# lvc_v2.net
KiCad netlist of a schematic drawn in EAGLE
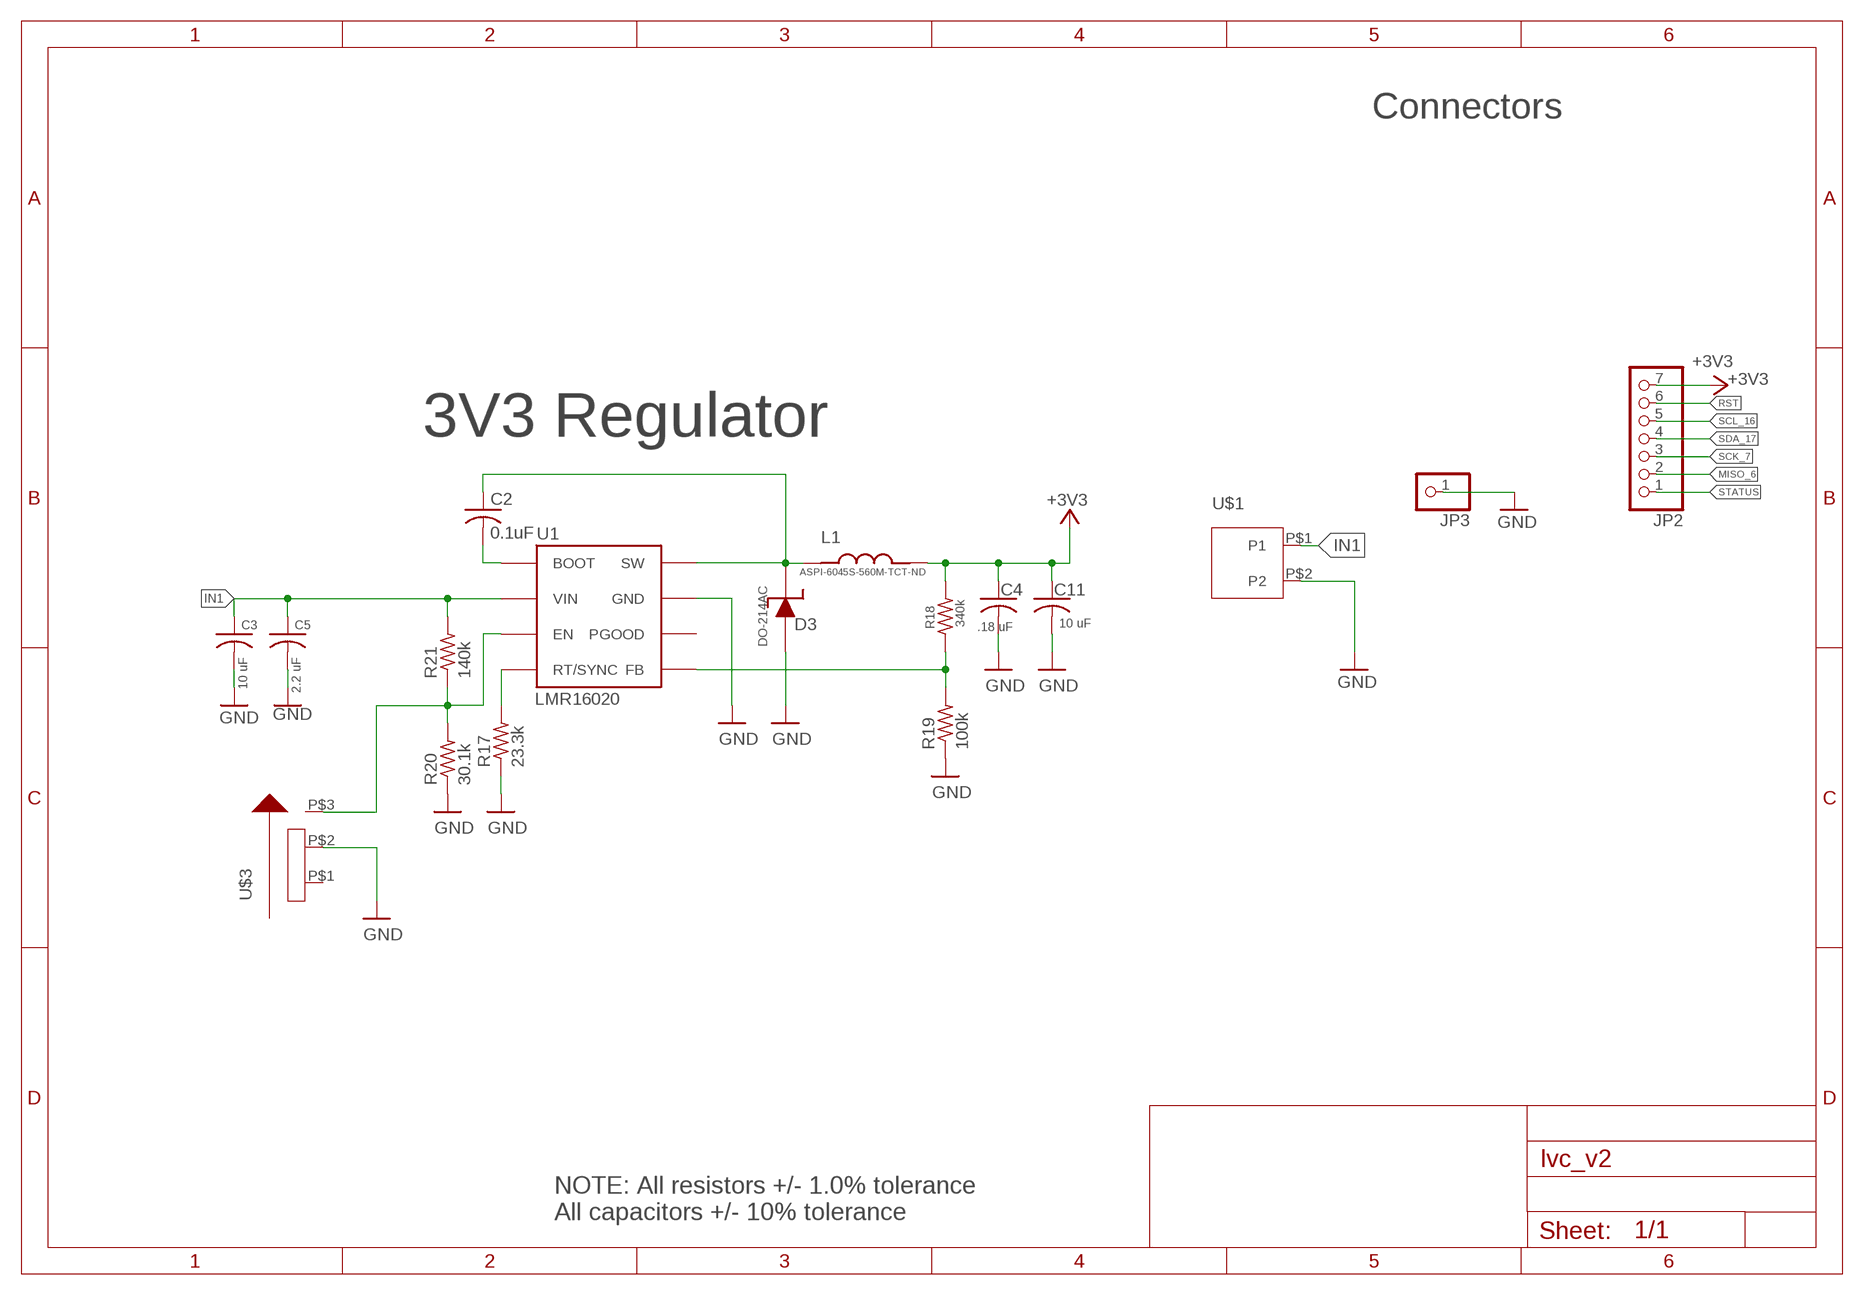
[diagram p0: schematic, sheet 1]

(export (version "E")
  (design (tool "Eeschema 10.0.6"))
  (components
    (comp (ref "C2")
      (value "0.1uF")
      (footprint "eagle-import:C0603")
      (libsource (lib "eagle-import") (part "C-USC0603"))
    )
    (comp (ref "C3")
      (value "10 uF")
      (footprint "eagle-import:C1210")
      (libsource (lib "eagle-import") (part "C-USC1210"))
    )
    (comp (ref "C4")
      (value ".18 uF")
      (footprint "eagle-import:C0603")
      (libsource (lib "eagle-import") (part "C-USC0603"))
    )
    (comp (ref "C5")
      (value "2.2 uF")
      (footprint "eagle-import:C1210")
      (libsource (lib "eagle-import") (part "C-USC1210"))
    )
    (comp (ref "C11")
      (value "10 uF")
      (footprint "eagle-import:C0603")
      (libsource (lib "eagle-import") (part "C-USC0603"))
    )
    (comp (ref "D3")
      (value "DO-214AC")
      (footprint "eagle-import:DO-214AC")
      (libsource (lib "eagle-import") (part "DO-214AC"))
    )
    (comp (ref "JP2")
      (value "PINHD-1X7")
      (footprint "eagle-import:1X07")
      (libsource (lib "eagle-import") (part "PINHD-1X7"))
    )
    (comp (ref "JP3")
      (value "PINHD-1X1")
      (footprint "eagle-import:1X01")
      (libsource (lib "eagle-import") (part "PINHD-1X1"))
    )
    (comp (ref "L1")
      (value "ASPI-6045S-560M-TCT-ND")
      (footprint "eagle-import:ABRACON")
      (libsource (lib "eagle-import") (part "ASPI-6045S-560M-TCT-ND"))
    )
    (comp (ref "R17")
      (value "23.3k")
      (footprint "eagle-import:R0603")
      (libsource (lib "eagle-import") (part "R-US_R0603"))
    )
    (comp (ref "R18")
      (value "340k")
      (footprint "eagle-import:R0603")
      (libsource (lib "eagle-import") (part "R-US_R0603"))
    )
    (comp (ref "R19")
      (value "100k")
      (footprint "eagle-import:R0603")
      (libsource (lib "eagle-import") (part "R-US_R0603"))
    )
    (comp (ref "R20")
      (value "30.1k")
      (footprint "eagle-import:R0603")
      (libsource (lib "eagle-import") (part "R-US_R0603"))
    )
    (comp (ref "R21")
      (value "140k")
      (footprint "eagle-import:R0603")
      (libsource (lib "eagle-import") (part "R-US_R0603"))
    )
    (comp (ref "U$1")
      (value "559350210")
      (footprint "eagle-import:559350210")
      (libsource (lib "eagle-import") (part "559350210"))
    )
    (comp (ref "U$3")
      (value "CL-SB-12B-01")
      (footprint "eagle-import:CL-SB-12B-01")
      (libsource (lib "eagle-import") (part "CL-SB-12B-01"))
    )
    (comp (ref "U1")
      (value "LMR16020")
      (footprint "eagle-import:SO8")
      (libsource (lib "eagle-import") (part "LMR16020"))
    )
  )
  (nets
    (net (code "1") (name "+3V3") (class "Default")
      (node (ref "C11") (pin "1") (pinfunction "1_1") (pintype "passive"))
      (node (ref "C4") (pin "1") (pinfunction "1_1") (pintype "passive"))
      (node (ref "JP2") (pin "7") (pinfunction "7_7") (pintype "passive"))
      (node (ref "L1") (pin "P$2") (pinfunction "P$2_P$2") (pintype "bidirectional"))
      (node (ref "R18") (pin "2") (pinfunction "2_2") (pintype "passive"))
    )
    (net (code "2") (name "GND") (class "Default")
      (node (ref "C11") (pin "2") (pinfunction "2_2") (pintype "passive"))
      (node (ref "C3") (pin "2") (pinfunction "2_2") (pintype "passive"))
      (node (ref "C4") (pin "2") (pinfunction "2_2") (pintype "passive"))
      (node (ref "C5") (pin "2") (pinfunction "2_2") (pintype "passive"))
      (node (ref "D3") (pin "P$1") (pinfunction "P$1_P$1") (pintype "bidirectional"))
      (node (ref "JP3") (pin "1") (pinfunction "1_1") (pintype "passive"))
      (node (ref "R17") (pin "1") (pinfunction "1_1") (pintype "passive"))
      (node (ref "R19") (pin "1") (pinfunction "1_1") (pintype "passive"))
      (node (ref "R20") (pin "1") (pinfunction "1_1") (pintype "passive"))
      (node (ref "U$1") (pin "P$2") (pinfunction "P2_P$2") (pintype "bidirectional"))
      (node (ref "U$3") (pin "P$2") (pinfunction "P2_P$2") (pintype "bidirectional"))
      (node (ref "U1") (pin "P$7") (pinfunction "GND_P$7") (pintype "bidirectional"))
      (node (ref "U1") (pin "PAD") (pinfunction "GND_PAD") (pintype "bidirectional"))
    )
    (net (code "3") (name "IN1") (class "Default")
      (node (ref "C3") (pin "1") (pinfunction "1_1") (pintype "passive"))
      (node (ref "C5") (pin "1") (pinfunction "1_1") (pintype "passive"))
      (node (ref "R21") (pin "2") (pinfunction "2_2") (pintype "passive"))
      (node (ref "U$1") (pin "P$1") (pinfunction "P1_P$1") (pintype "bidirectional"))
      (node (ref "U1") (pin "P$2") (pinfunction "VIN_P$2") (pintype "bidirectional"))
    )
    (net (code "4") (name "MISO_6") (class "Default")
      (node (ref "JP2") (pin "2") (pinfunction "2_2") (pintype "passive"))
    )
    (net (code "5") (name "Net-(U$3-P3)") (class "Default")
      (node (ref "R20") (pin "2") (pinfunction "2_2") (pintype "passive"))
      (node (ref "R21") (pin "1") (pinfunction "1_1") (pintype "passive"))
      (node (ref "U$3") (pin "P$3") (pinfunction "P3_P$3") (pintype "bidirectional"))
      (node (ref "U1") (pin "P$3") (pinfunction "EN_P$3") (pintype "bidirectional"))
    )
    (net (code "6") (name "Net-(U1-BOOT)") (class "Default")
      (node (ref "C2") (pin "2") (pinfunction "2_2") (pintype "passive"))
      (node (ref "U1") (pin "P$1") (pinfunction "BOOT_P$1") (pintype "bidirectional"))
    )
    (net (code "7") (name "Net-(U1-FB)") (class "Default")
      (node (ref "R18") (pin "1") (pinfunction "1_1") (pintype "passive"))
      (node (ref "R19") (pin "2") (pinfunction "2_2") (pintype "passive"))
      (node (ref "U1") (pin "P$5") (pinfunction "FB_P$5") (pintype "bidirectional"))
    )
    (net (code "8") (name "Net-(U1-RT{slash}SYNC)") (class "Default")
      (node (ref "R17") (pin "2") (pinfunction "2_2") (pintype "passive"))
      (node (ref "U1") (pin "P$4") (pinfunction "RT/SYNC_P$4") (pintype "bidirectional"))
    )
    (net (code "9") (name "Net-(U1-SW)") (class "Default")
      (node (ref "C2") (pin "1") (pinfunction "1_1") (pintype "passive"))
      (node (ref "D3") (pin "P$2") (pinfunction "P$2_P$2") (pintype "bidirectional"))
      (node (ref "L1") (pin "P$1") (pinfunction "P$1_P$1") (pintype "bidirectional"))
      (node (ref "U1") (pin "P$8") (pinfunction "SW_P$8") (pintype "bidirectional"))
    )
    (net (code "10") (name "RST") (class "Default")
      (node (ref "JP2") (pin "6") (pinfunction "6_6") (pintype "passive"))
    )
    (net (code "11") (name "SCK_7") (class "Default")
      (node (ref "JP2") (pin "3") (pinfunction "3_3") (pintype "passive"))
    )
    (net (code "12") (name "SCL_16") (class "Default")
      (node (ref "JP2") (pin "5") (pinfunction "5_5") (pintype "passive"))
    )
    (net (code "13") (name "SDA_17") (class "Default")
      (node (ref "JP2") (pin "4") (pinfunction "4_4") (pintype "passive"))
    )
    (net (code "14") (name "STATUS") (class "Default")
      (node (ref "JP2") (pin "1") (pinfunction "1_1") (pintype "passive"))
    )
    (net (code "15") (name "unconnected-(U$3-P1-PadP$1)") (class "Default")
      (node (ref "U$3") (pin "P$1") (pinfunction "P1_P$1") (pintype "bidirectional"))
    )
    (net (code "16") (name "unconnected-(U1-PGOOD-PadP$6)") (class "Default")
      (node (ref "U1") (pin "P$6") (pinfunction "PGOOD_P$6") (pintype "bidirectional"))
    )
  )
)
